# DOORLOCK_alter.net
KiCad netlist of a schematic drawn in EAGLE
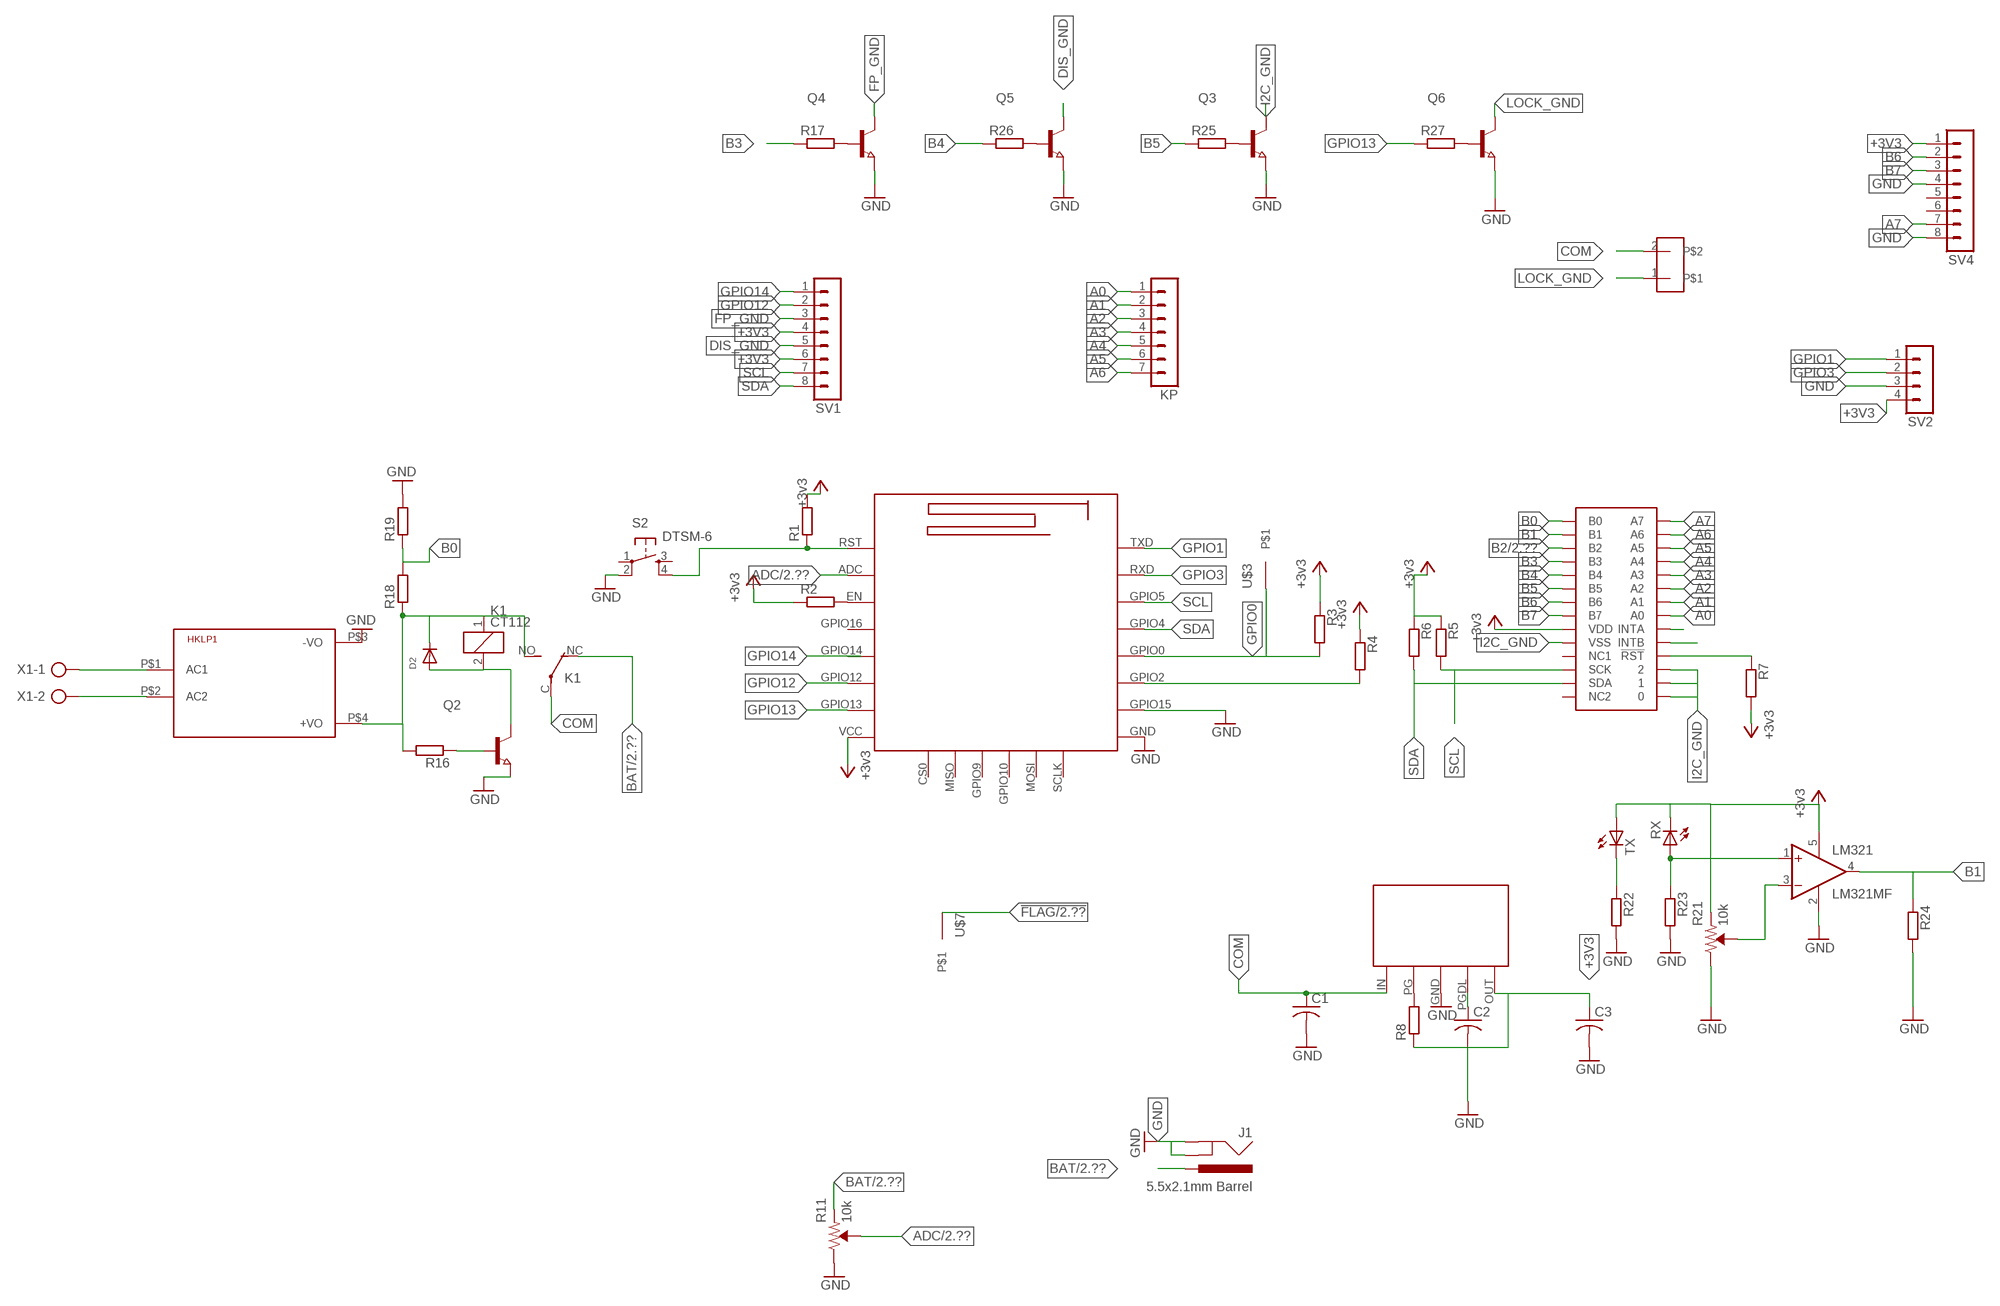
[diagram p0: schematic, sheet 1]
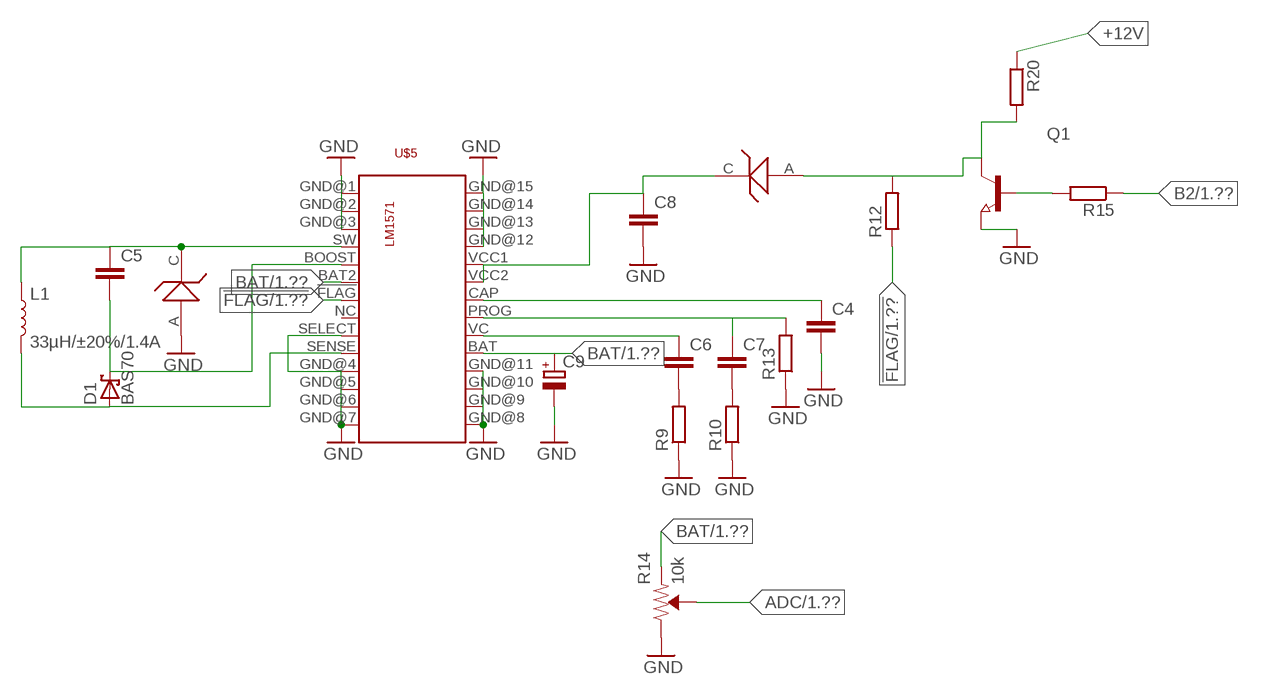
[diagram p1: schematic, sheet 2]

(export (version "E")
  (design (tool "Eeschema 10.0.6"))
  (components
    (comp (ref "C4")
      (value "C-EUC0805")
      (footprint "eagle-import:C0805")
      (libsource (lib "eagle-import") (part "C-EUC0805"))
    )
    (comp (ref "C5")
      (value "C-EUC0805")
      (footprint "eagle-import:C0805")
      (libsource (lib "eagle-import") (part "C-EUC0805"))
    )
    (comp (ref "C6")
      (value "C-EUC0805")
      (footprint "eagle-import:C0805")
      (libsource (lib "eagle-import") (part "C-EUC0805"))
    )
    (comp (ref "C7")
      (value "C-EUC0805")
      (footprint "eagle-import:C0805")
      (libsource (lib "eagle-import") (part "C-EUC0805"))
    )
    (comp (ref "C8")
      (value "C-EUC0805")
      (footprint "eagle-import:C0805")
      (libsource (lib "eagle-import") (part "C-EUC0805"))
    )
    (comp (ref "C9")
      (value "CPOL-EUCT3216")
      (footprint "eagle-import:CT3216")
      (libsource (lib "eagle-import") (part "CPOL-EUCT3216"))
    )
    (comp (ref "D1")
      (value "BAS70")
      (footprint "eagle-import:SOT23")
      (libsource (lib "eagle-import") (part "BAS70"))
    )
    (comp (ref "D3")
      (value "MBRM120T3")
      (footprint "eagle-import:MBRM120T3")
      (libsource (lib "eagle-import") (part "MBRM120T3"))
    )
    (comp (ref "L1")
      (value "33µH/±20%/1.4A")
      (footprint "eagle-import:SRN6045")
      (libsource (lib "eagle-import") (part "INDUCTOR-SRN6045-33UH"))
    )
    (comp (ref "Q1")
      (value "NPN-TRANSISTOR_SOT89")
      (footprint "eagle-import:SOT89")
      (libsource (lib "eagle-import") (part "NPN-TRANSISTOR_SOT89"))
    )
    (comp (ref "R9")
      (value "R-EU_0204/2V")
      (footprint "eagle-import:0204V")
      (libsource (lib "eagle-import") (part "R-EU_0204/2V"))
    )
    (comp (ref "R10")
      (value "R-EU_0204/2V")
      (footprint "eagle-import:0204V")
      (libsource (lib "eagle-import") (part "R-EU_0204/2V"))
    )
    (comp (ref "R12")
      (value "R-EU_0204/2V")
      (footprint "eagle-import:0204V")
      (libsource (lib "eagle-import") (part "R-EU_0204/2V"))
    )
    (comp (ref "R13")
      (value "R-EU_0204/2V")
      (footprint "eagle-import:0204V")
      (libsource (lib "eagle-import") (part "R-EU_0204/2V"))
    )
    (comp (ref "R14")
      (value "10k")
      (footprint "eagle-import:TRIMPOT-SMD-TC33X")
      (libsource (lib "eagle-import") (part "TRIMPOT-SMD-3MM-OPEN-1/10W-25%"))
    )
    (comp (ref "R15")
      (value "R-EU_0204/2V")
      (footprint "eagle-import:0204V")
      (libsource (lib "eagle-import") (part "R-EU_0204/2V"))
    )
    (comp (ref "R20")
      (value "R-EU_0204/2V")
      (footprint "eagle-import:0204V")
      (libsource (lib "eagle-import") (part "R-EU_0204/2V"))
    )
    (comp (ref "U$5")
      (value "LM1571")
      (footprint "eagle-import:LT1571")
      (libsource (lib "eagle-import") (part "LM1571"))
    )
    (comp (ref "U$6")
      (value "MBRM120T3")
      (footprint "eagle-import:MBRM120T3")
      (libsource (lib "eagle-import") (part "MBRM120T3"))
    )
    (comp (ref "C1")
      (value "C-USC1206")
      (footprint "eagle-import:C1206")
      (libsource (lib "eagle-import") (part "C-USC1206"))
    )
    (comp (ref "C2")
      (value "C-USC1206")
      (footprint "eagle-import:C1206")
      (libsource (lib "eagle-import") (part "C-USC1206"))
    )
    (comp (ref "C3")
      (value "C-USC1206")
      (footprint "eagle-import:C1206")
      (libsource (lib "eagle-import") (part "C-USC1206"))
    )
    (comp (ref "D2")
      (value "DIODESOD-123")
      (footprint "eagle-import:SOD-123")
      (libsource (lib "eagle-import") (part "DIODESOD-123"))
    )
    (comp (ref "HKLP1")
      (value "HKLPM01")
      (footprint "eagle-import:HKLPM01")
      (libsource (lib "eagle-import") (part "HKLPM01"))
    )
    (comp (ref "J1")
      (value "5.5x2.1mm Barrel")
      (footprint "eagle-import:POWER_JACK_SMD")
      (libsource (lib "eagle-import") (part "POWER_JACKSMD"))
    )
    (comp (ref "K1")
      (value "CT112")
      (footprint "eagle-import:CT-SLIM")
      (libsource (lib "eagle-import") (part "CT112"))
    )
    (comp (ref "KP")
      (value "MA07-1")
      (footprint "eagle-import:MA07-1")
      (libsource (lib "eagle-import") (part "MA07-1"))
    )
    (comp (ref "LM321")
      (value "LM321MF")
      (footprint "eagle-import:SOT23-5")
      (libsource (lib "eagle-import") (part "LM321?MF"))
    )
    (comp (ref "MP2014")
      (value "MP2014")
      (footprint "eagle-import:MP2014")
      (libsource (lib "eagle-import") (part "MP2014"))
    )
    (comp (ref "Q2")
      (value "NPN-TRANSISTOR_SOT89")
      (footprint "eagle-import:SOT89")
      (libsource (lib "eagle-import") (part "NPN-TRANSISTOR_SOT89"))
    )
    (comp (ref "Q3")
      (value "NPN-TRANSISTOR_SOT89")
      (footprint "eagle-import:SOT89")
      (libsource (lib "eagle-import") (part "NPN-TRANSISTOR_SOT89"))
    )
    (comp (ref "Q4")
      (value "NPN-TRANSISTOR_SOT89")
      (footprint "eagle-import:SOT89")
      (libsource (lib "eagle-import") (part "NPN-TRANSISTOR_SOT89"))
    )
    (comp (ref "Q5")
      (value "NPN-TRANSISTOR_SOT89")
      (footprint "eagle-import:SOT89")
      (libsource (lib "eagle-import") (part "NPN-TRANSISTOR_SOT89"))
    )
    (comp (ref "Q6")
      (value "NPN-TRANSISTOR_SOT89")
      (footprint "eagle-import:SOT89")
      (libsource (lib "eagle-import") (part "NPN-TRANSISTOR_SOT89"))
    )
    (comp (ref "R1")
      (value "R-EU_0204/2V")
      (footprint "eagle-import:0204V")
      (libsource (lib "eagle-import") (part "resistor_R-EU_0204/2V"))
    )
    (comp (ref "R2")
      (value "R-EU_0204/2V")
      (footprint "eagle-import:0204V")
      (libsource (lib "eagle-import") (part "resistor_R-EU_0204/2V"))
    )
    (comp (ref "R3")
      (value "R-EU_0204/2V")
      (footprint "eagle-import:0204V")
      (libsource (lib "eagle-import") (part "resistor_R-EU_0204/2V"))
    )
    (comp (ref "R4")
      (value "R-EU_0204/2V")
      (footprint "eagle-import:0204V")
      (libsource (lib "eagle-import") (part "resistor_R-EU_0204/2V"))
    )
    (comp (ref "R5")
      (value "R-EU_0204/2V")
      (footprint "eagle-import:0204V")
      (libsource (lib "eagle-import") (part "resistor_R-EU_0204/2V"))
    )
    (comp (ref "R6")
      (value "R-EU_0204/2V")
      (footprint "eagle-import:0204V")
      (libsource (lib "eagle-import") (part "resistor_R-EU_0204/2V"))
    )
    (comp (ref "R7")
      (value "R-EU_0204/2V")
      (footprint "eagle-import:0204V")
      (libsource (lib "eagle-import") (part "resistor_R-EU_0204/2V"))
    )
    (comp (ref "R8")
      (value "R-EU_0204/2V")
      (footprint "eagle-import:0204V")
      (libsource (lib "eagle-import") (part "resistor_R-EU_0204/2V"))
    )
    (comp (ref "R11")
      (value "10k")
      (footprint "eagle-import:TRIMPOT-SMD-TC33X")
      (libsource (lib "eagle-import") (part "TRIMPOT-SMD-3MM-OPEN-1/10W-25%"))
    )
    (comp (ref "R16")
      (value "R-EU_0204/2V")
      (footprint "eagle-import:0204V")
      (libsource (lib "eagle-import") (part "resistor_R-EU_0204/2V"))
    )
    (comp (ref "R17")
      (value "R-EU_0204/2V")
      (footprint "eagle-import:0204V")
      (libsource (lib "eagle-import") (part "resistor_R-EU_0204/2V"))
    )
    (comp (ref "R18")
      (value "R-EU_0204/2V")
      (footprint "eagle-import:0204V")
      (libsource (lib "eagle-import") (part "resistor_R-EU_0204/2V"))
    )
    (comp (ref "R19")
      (value "R-EU_0204/2V")
      (footprint "eagle-import:0204V")
      (libsource (lib "eagle-import") (part "resistor_R-EU_0204/2V"))
    )
    (comp (ref "R21")
      (value "10k")
      (footprint "eagle-import:TRIMPOT-SMD-TC33X")
      (libsource (lib "eagle-import") (part "TRIMPOT-SMD-3MM-OPEN-1/10W-25%"))
    )
    (comp (ref "R22")
      (value "R-EU_0204/2V")
      (footprint "eagle-import:0204V")
      (libsource (lib "eagle-import") (part "resistor_R-EU_0204/2V"))
    )
    (comp (ref "R23")
      (value "R-EU_0204/2V")
      (footprint "eagle-import:0204V")
      (libsource (lib "eagle-import") (part "resistor_R-EU_0204/2V"))
    )
    (comp (ref "R24")
      (value "R-EU_0204/2V")
      (footprint "eagle-import:0204V")
      (libsource (lib "eagle-import") (part "resistor_R-EU_0204/2V"))
    )
    (comp (ref "R25")
      (value "R-EU_0204/2V")
      (footprint "eagle-import:0204V")
      (libsource (lib "eagle-import") (part "resistor_R-EU_0204/2V"))
    )
    (comp (ref "R26")
      (value "R-EU_0204/2V")
      (footprint "eagle-import:0204V")
      (libsource (lib "eagle-import") (part "resistor_R-EU_0204/2V"))
    )
    (comp (ref "R27")
      (value "R-EU_0204/2V")
      (footprint "eagle-import:0204V")
      (libsource (lib "eagle-import") (part "resistor_R-EU_0204/2V"))
    )
    (comp (ref "RX")
      (value "LED5MM")
      (footprint "eagle-import:LED5MM")
      (libsource (lib "eagle-import") (part "LED5MM"))
    )
    (comp (ref "S2")
      (value "DTSM-6")
      (footprint "eagle-import:DTSM-6")
      (libsource (lib "eagle-import") (part "DTSM-6"))
    )
    (comp (ref "SV1")
      (value "MA08-1")
      (footprint "eagle-import:MA08-1")
      (libsource (lib "eagle-import") (part "MA08-1"))
    )
    (comp (ref "SV2")
      (value "MA04-1")
      (footprint "eagle-import:MA04-1")
      (libsource (lib "eagle-import") (part "MA04-1"))
    )
    (comp (ref "SV4")
      (value "MA08-1")
      (footprint "eagle-import:MA08-1")
      (libsource (lib "eagle-import") (part "MA08-1"))
    )
    (comp (ref "TX")
      (value "LED5MM")
      (footprint "eagle-import:LED5MM")
      (libsource (lib "eagle-import") (part "LED5MM"))
    )
    (comp (ref "U$1")
      (value "ESP12E")
      (footprint "eagle-import:ESP-12E")
      (libsource (lib "eagle-import") (part "ESP12E"))
    )
    (comp (ref "U$2")
      (value "MCF23017")
      (footprint "eagle-import:MAX23017")
      (libsource (lib "eagle-import") (part "MCF23017"))
    )
    (comp (ref "U$3") (value "M1") (footprint "eagle-import:M1") (libsource (lib "eagle-import") (part "M1")))
    (comp (ref "U$4")
      (value "MALE2PIN")
      (footprint "eagle-import:MALE2PIN")
      (libsource (lib "eagle-import") (part "MALE2PIN"))
    )
    (comp (ref "U$7") (value "M1") (footprint "eagle-import:M1") (libsource (lib "eagle-import") (part "M1")))
    (comp (ref "X1")
      (value "AK500/2-H")
      (footprint "eagle-import:AK500_2-H")
      (libsource (lib "eagle-import") (part "AK500/2-H"))
    )
  )
  (nets
    (net (code "1") (name "+3V3") (class "Default")
      (node (ref "C3") (pin "1") (pinfunction "1_1") (pintype "passive"))
      (node (ref "LM321") (pin "5") (pinfunction "V+_5") (pintype "power_in"))
      (node (ref "MP2014") (pin "OUT") (pinfunction "P$5_OUT") (pintype "bidirectional"))
      (node (ref "R1") (pin "2") (pinfunction "2_2") (pintype "passive"))
      (node (ref "R2") (pin "1") (pinfunction "1_1") (pintype "passive"))
      (node (ref "R21") (pin "3") (pinfunction "CCW_3") (pintype "passive"))
      (node (ref "R3") (pin "1") (pinfunction "1_1") (pintype "passive"))
      (node (ref "R4") (pin "1") (pinfunction "1_1") (pintype "passive"))
      (node (ref "R5") (pin "1") (pinfunction "1_1") (pintype "passive"))
      (node (ref "R6") (pin "1") (pinfunction "1_1") (pintype "passive"))
      (node (ref "R7") (pin "2") (pinfunction "2_2") (pintype "passive"))
      (node (ref "R8") (pin "1") (pinfunction "1_1") (pintype "passive"))
      (node (ref "RX") (pin "K") (pinfunction "C_K") (pintype "passive"))
      (node (ref "SV1") (pin "4") (pinfunction "4_4") (pintype "passive"))
      (node (ref "SV1") (pin "6") (pinfunction "6_6") (pintype "passive"))
      (node (ref "SV2") (pin "4") (pinfunction "4_4") (pintype "passive"))
      (node (ref "SV4") (pin "1") (pinfunction "1_1") (pintype "passive"))
      (node (ref "TX") (pin "A") (pinfunction "A_A") (pintype "passive"))
      (node (ref "U$1") (pin "VCC") (pinfunction "P$8_VCC") (pintype "bidirectional"))
      (node (ref "U$2") (pin "P$9") (pinfunction "VDD_P$9") (pintype "bidirectional"))
    )
    (net (code "2") (name "+12V") (class "Default")
      (node (ref "D2") (pin "C") (pinfunction "C_C") (pintype "passive"))
      (node (ref "HKLP1") (pin "P$4") (pinfunction "+VO_P$4") (pintype "bidirectional"))
      (node (ref "K1") (pin "1") (pinfunction "1_1") (pintype "passive"))
      (node (ref "K1") (pin "NO") (pinfunction "S_NO") (pintype "passive"))
      (node (ref "R16") (pin "2") (pinfunction "2_2") (pintype "passive"))
      (node (ref "R18") (pin "1") (pinfunction "1_1") (pintype "passive"))
      (node (ref "R20") (pin "1") (pinfunction "1_1") (pintype "passive"))
    )
    (net (code "3") (name "A0") (class "Default")
      (node (ref "KP") (pin "1") (pinfunction "1_1") (pintype "passive"))
      (node (ref "U$2") (pin "P$21") (pinfunction "A0_P$21") (pintype "bidirectional"))
    )
    (net (code "4") (name "A1") (class "Default")
      (node (ref "KP") (pin "2") (pinfunction "2_2") (pintype "passive"))
      (node (ref "U$2") (pin "P$22") (pinfunction "A1_P$22") (pintype "bidirectional"))
    )
    (net (code "5") (name "A2") (class "Default")
      (node (ref "KP") (pin "3") (pinfunction "3_3") (pintype "passive"))
      (node (ref "U$2") (pin "P$23") (pinfunction "A2_P$23") (pintype "bidirectional"))
    )
    (net (code "6") (name "A3") (class "Default")
      (node (ref "KP") (pin "4") (pinfunction "4_4") (pintype "passive"))
      (node (ref "U$2") (pin "P$24") (pinfunction "A3_P$24") (pintype "bidirectional"))
    )
    (net (code "7") (name "A4") (class "Default")
      (node (ref "KP") (pin "5") (pinfunction "5_5") (pintype "passive"))
      (node (ref "U$2") (pin "P$25") (pinfunction "A4_P$25") (pintype "bidirectional"))
    )
    (net (code "8") (name "A5") (class "Default")
      (node (ref "KP") (pin "6") (pinfunction "6_6") (pintype "passive"))
      (node (ref "U$2") (pin "P$26") (pinfunction "A5_P$26") (pintype "bidirectional"))
    )
    (net (code "9") (name "A6") (class "Default")
      (node (ref "KP") (pin "7") (pinfunction "7_7") (pintype "passive"))
      (node (ref "U$2") (pin "P$27") (pinfunction "A6_P$27") (pintype "bidirectional"))
    )
    (net (code "10") (name "A7") (class "Default")
      (node (ref "SV4") (pin "7") (pinfunction "7_7") (pintype "passive"))
      (node (ref "U$2") (pin "P$28") (pinfunction "A7_P$28") (pintype "bidirectional"))
    )
    (net (code "11") (name "ADC") (class "Default")
      (node (ref "R11") (pin "2") (pinfunction "WIPER_2") (pintype "passive"))
      (node (ref "R14") (pin "2") (pinfunction "WIPER_2") (pintype "passive"))
      (node (ref "U$1") (pin "ADC") (pinfunction "P$2_ADC") (pintype "bidirectional"))
    )
    (net (code "12") (name "B0") (class "Default")
      (node (ref "R18") (pin "2") (pinfunction "2_2") (pintype "passive"))
      (node (ref "R19") (pin "1") (pinfunction "1_1") (pintype "passive"))
      (node (ref "U$2") (pin "P$1") (pinfunction "B0_P$1") (pintype "bidirectional"))
    )
    (net (code "13") (name "B1") (class "Default")
      (node (ref "LM321") (pin "4") (pinfunction "OUT_4") (pintype "output"))
      (node (ref "R24") (pin "1") (pinfunction "1_1") (pintype "passive"))
      (node (ref "U$2") (pin "P$2") (pinfunction "B1_P$2") (pintype "bidirectional"))
    )
    (net (code "14") (name "B2") (class "Default")
      (node (ref "R15") (pin "1") (pinfunction "1_1") (pintype "passive"))
      (node (ref "U$2") (pin "P$3") (pinfunction "B2_P$3") (pintype "bidirectional"))
    )
    (net (code "15") (name "B3") (class "Default")
      (node (ref "R17") (pin "1") (pinfunction "1_1") (pintype "passive"))
      (node (ref "U$2") (pin "P$4") (pinfunction "B3_P$4") (pintype "bidirectional"))
    )
    (net (code "16") (name "B4") (class "Default")
      (node (ref "R26") (pin "1") (pinfunction "1_1") (pintype "passive"))
      (node (ref "U$2") (pin "P$5") (pinfunction "B4_P$5") (pintype "bidirectional"))
    )
    (net (code "17") (name "B5") (class "Default")
      (node (ref "R25") (pin "1") (pinfunction "1_1") (pintype "passive"))
      (node (ref "U$2") (pin "P$6") (pinfunction "B5_P$6") (pintype "bidirectional"))
    )
    (net (code "18") (name "B6") (class "Default")
      (node (ref "SV4") (pin "2") (pinfunction "2_2") (pintype "passive"))
      (node (ref "U$2") (pin "P$7") (pinfunction "B6_P$7") (pintype "bidirectional"))
    )
    (net (code "19") (name "B7") (class "Default")
      (node (ref "SV4") (pin "3") (pinfunction "3_3") (pintype "passive"))
      (node (ref "U$2") (pin "P$8") (pinfunction "B7_P$8") (pintype "bidirectional"))
    )
    (net (code "20") (name "BAT") (class "Default")
      (node (ref "C9") (pin "+") (pinfunction "+_+") (pintype "passive"))
      (node (ref "J1") (pin "VIN0") (pinfunction "PWR_VIN0") (pintype "bidirectional"))
      (node (ref "K1") (pin "NC") (pinfunction "O_NC") (pintype "passive"))
      (node (ref "R11") (pin "3") (pinfunction "CCW_3") (pintype "passive"))
      (node (ref "R14") (pin "3") (pinfunction "CCW_3") (pintype "passive"))
      (node (ref "U$5") (pin "BAT") (pinfunction "P$19_BAT") (pintype "bidirectional"))
      (node (ref "U$5") (pin "BAT2") (pinfunction "P$6_BAT2") (pintype "bidirectional"))
    )
    (net (code "21") (name "COM") (class "Default")
      (node (ref "C1") (pin "1") (pinfunction "1_1") (pintype "passive"))
      (node (ref "K1") (pin "C") (pinfunction "P_C") (pintype "passive"))
      (node (ref "MP2014") (pin "IN") (pinfunction "P$1_IN") (pintype "bidirectional"))
      (node (ref "U$4") (pin "2") (pinfunction "P$2_2") (pintype "bidirectional"))
    )
    (net (code "22") (name "DIS_GND") (class "Default")
      (node (ref "Q5") (pin "2") (pinfunction "C_2") (pintype "passive"))
      (node (ref "SV1") (pin "5") (pinfunction "5_5") (pintype "passive"))
    )
    (net (code "23") (name "FP_GND") (class "Default")
      (node (ref "Q4") (pin "2") (pinfunction "C_2") (pintype "passive"))
      (node (ref "SV1") (pin "3") (pinfunction "3_3") (pintype "passive"))
    )
    (net (code "24") (name "GND") (class "Default")
      (node (ref "C1") (pin "2") (pinfunction "2_2") (pintype "passive"))
      (node (ref "C2") (pin "2") (pinfunction "2_2") (pintype "passive"))
      (node (ref "C3") (pin "2") (pinfunction "2_2") (pintype "passive"))
      (node (ref "C4") (pin "2") (pinfunction "2_2") (pintype "passive"))
      (node (ref "C8") (pin "2") (pinfunction "2_2") (pintype "passive"))
      (node (ref "C9") (pin "-") (pinfunction "-_-") (pintype "passive"))
      (node (ref "HKLP1") (pin "P$3") (pinfunction "-VO_P$3") (pintype "bidirectional"))
      (node (ref "J1") (pin "GND") (pinfunction "GNDBREAK_GND") (pintype "bidirectional"))
      (node (ref "J1") (pin "P$4") (pinfunction "GND_P$4") (pintype "bidirectional"))
      (node (ref "LM321") (pin "2") (pinfunction "V-_2") (pintype "power_in"))
      (node (ref "MP2014") (pin "GND") (pinfunction "P$3_GND") (pintype "bidirectional"))
      (node (ref "Q1") (pin "3") (pinfunction "E_3") (pintype "passive"))
      (node (ref "Q2") (pin "3") (pinfunction "E_3") (pintype "passive"))
      (node (ref "Q3") (pin "3") (pinfunction "E_3") (pintype "passive"))
      (node (ref "Q4") (pin "3") (pinfunction "E_3") (pintype "passive"))
      (node (ref "Q5") (pin "3") (pinfunction "E_3") (pintype "passive"))
      (node (ref "Q6") (pin "3") (pinfunction "E_3") (pintype "passive"))
      (node (ref "R10") (pin "1") (pinfunction "1_1") (pintype "passive"))
      (node (ref "R11") (pin "1") (pinfunction "CW_1") (pintype "passive"))
      (node (ref "R13") (pin "1") (pinfunction "1_1") (pintype "passive"))
      (node (ref "R14") (pin "1") (pinfunction "CW_1") (pintype "passive"))
      (node (ref "R19") (pin "2") (pinfunction "2_2") (pintype "passive"))
      (node (ref "R21") (pin "1") (pinfunction "CW_1") (pintype "passive"))
      (node (ref "R22") (pin "2") (pinfunction "2_2") (pintype "passive"))
      (node (ref "R23") (pin "2") (pinfunction "2_2") (pintype "passive"))
      (node (ref "R24") (pin "2") (pinfunction "2_2") (pintype "passive"))
      (node (ref "R9") (pin "1") (pinfunction "1_1") (pintype "passive"))
      (node (ref "S2") (pin "2") (pinfunction "2_2") (pintype "passive"))
      (node (ref "SV2") (pin "3") (pinfunction "3_3") (pintype "passive"))
      (node (ref "SV4") (pin "4") (pinfunction "4_4") (pintype "passive"))
      (node (ref "SV4") (pin "8") (pinfunction "8_8") (pintype "passive"))
      (node (ref "U$1") (pin "GND") (pinfunction "P$15_GND") (pintype "bidirectional"))
      (node (ref "U$1") (pin "GPIO15") (pinfunction "P$16_GPIO15") (pintype "bidirectional"))
      (node (ref "U$5") (pin "GND@1") (pinfunction "P$1_GND@1") (pintype "bidirectional"))
      (node (ref "U$5") (pin "GND@10") (pinfunction "P$17_GND@10") (pintype "bidirectional"))
      (node (ref "U$5") (pin "GND@11") (pinfunction "P$18_GND@11") (pintype "bidirectional"))
      (node (ref "U$5") (pin "GND@12") (pinfunction "P$25_GND@12") (pintype "bidirectional"))
      (node (ref "U$5") (pin "GND@13") (pinfunction "P$26_GND@13") (pintype "bidirectional"))
      (node (ref "U$5") (pin "GND@14") (pinfunction "P$27_GND@14") (pintype "bidirectional"))
      (node (ref "U$5") (pin "GND@15") (pinfunction "P$28_GND@15") (pintype "bidirectional"))
      (node (ref "U$5") (pin "GND@2") (pinfunction "P$2_GND@2") (pintype "bidirectional"))
      (node (ref "U$5") (pin "GND@3") (pinfunction "P$3_GND@3") (pintype "bidirectional"))
      (node (ref "U$5") (pin "GND@4") (pinfunction "P$11_GND@4") (pintype "bidirectional"))
      (node (ref "U$5") (pin "GND@5") (pinfunction "P$12_GND@5") (pintype "bidirectional"))
      (node (ref "U$5") (pin "GND@6") (pinfunction "P$13_GND@6") (pintype "bidirectional"))
      (node (ref "U$5") (pin "GND@7") (pinfunction "P$14_GND@7") (pintype "bidirectional"))
      (node (ref "U$5") (pin "GND@8") (pinfunction "P$15_GND@8") (pintype "bidirectional"))
      (node (ref "U$5") (pin "GND@9") (pinfunction "P$16_GND@9") (pintype "bidirectional"))
      (node (ref "U$5") (pin "SELECT") (pinfunction "P$9_SELECT") (pintype "bidirectional"))
      (node (ref "U$6") (pin "A") (pinfunction "A_A") (pintype "bidirectional"))
    )
    (net (code "25") (name "GPIO0") (class "Default")
      (node (ref "R3") (pin "2") (pinfunction "2_2") (pintype "passive"))
      (node (ref "U$1") (pin "GPIO0") (pinfunction "P$18_GPIO0") (pintype "bidirectional"))
      (node (ref "U$3") (pin "P$1") (pinfunction "P$1_P$1") (pintype "bidirectional"))
    )
    (net (code "26") (name "GPIO1") (class "Default")
      (node (ref "SV2") (pin "1") (pinfunction "1_1") (pintype "passive"))
      (node (ref "U$1") (pin "TXD") (pinfunction "P$22_TXD") (pintype "bidirectional"))
    )
    (net (code "27") (name "GPIO3") (class "Default")
      (node (ref "SV2") (pin "2") (pinfunction "2_2") (pintype "passive"))
      (node (ref "U$1") (pin "RXD") (pinfunction "P$21_RXD") (pintype "bidirectional"))
    )
    (net (code "28") (name "GPIO12") (class "Default")
      (node (ref "SV1") (pin "2") (pinfunction "2_2") (pintype "passive"))
      (node (ref "U$1") (pin "GPIO12") (pinfunction "P$6_GPIO12") (pintype "bidirectional"))
    )
    (net (code "29") (name "GPIO13") (class "Default")
      (node (ref "R27") (pin "1") (pinfunction "1_1") (pintype "passive"))
      (node (ref "U$1") (pin "GPIO13") (pinfunction "P$7_GPIO13") (pintype "bidirectional"))
    )
    (net (code "30") (name "GPIO14") (class "Default")
      (node (ref "SV1") (pin "1") (pinfunction "1_1") (pintype "passive"))
      (node (ref "U$1") (pin "GPIO14") (pinfunction "P$5_GPIO14") (pintype "bidirectional"))
    )
    (net (code "31") (name "I2C_GND") (class "Default")
      (node (ref "Q3") (pin "2") (pinfunction "C_2") (pintype "passive"))
      (node (ref "U$2") (pin "P$10") (pinfunction "VSS_P$10") (pintype "bidirectional"))
      (node (ref "U$2") (pin "P$15") (pinfunction "0_P$15") (pintype "bidirectional"))
      (node (ref "U$2") (pin "P$16") (pinfunction "1_P$16") (pintype "bidirectional"))
      (node (ref "U$2") (pin "P$17") (pinfunction "2_P$17") (pintype "bidirectional"))
    )
    (net (code "32") (name "LOCK_GND") (class "Default")
      (node (ref "Q6") (pin "2") (pinfunction "C_2") (pintype "passive"))
      (node (ref "U$4") (pin "1") (pinfunction "P$1_1") (pintype "bidirectional"))
    )
    (net (code "33") (name "Net-(C6-Pad2)") (class "Default")
      (node (ref "C6") (pin "2") (pinfunction "2_2") (pintype "passive"))
      (node (ref "R9") (pin "2") (pinfunction "2_2") (pintype "passive"))
    )
    (net (code "34") (name "Net-(C7-Pad2)") (class "Default")
      (node (ref "C7") (pin "2") (pinfunction "2_2") (pintype "passive"))
      (node (ref "R10") (pin "2") (pinfunction "2_2") (pintype "passive"))
    )
    (net (code "35") (name "Net-(D1-A)") (class "Default")
      (node (ref "D1") (pin "1") (pinfunction "A_1") (pintype "passive"))
      (node (ref "L1") (pin "2") (pinfunction "2_2") (pintype "passive"))
      (node (ref "U$5") (pin "SENSE") (pinfunction "P$10_SENSE") (pintype "bidirectional"))
    )
    (net (code "36") (name "Net-(D1-C)") (class "Default")
      (node (ref "C5") (pin "2") (pinfunction "2_2") (pintype "passive"))
      (node (ref "D1") (pin "3") (pinfunction "C_3") (pintype "passive"))
      (node (ref "U$5") (pin "BOOST") (pinfunction "P$5_BOOST") (pintype "bidirectional"))
    )
    (net (code "37") (name "Net-(HKLP1-AC1)") (class "Default")
      (node (ref "HKLP1") (pin "P$1") (pinfunction "AC1_P$1") (pintype "bidirectional"))
      (node (ref "X1") (pin "1") (pinfunction "KL_1") (pintype "passive"))
    )
    (net (code "38") (name "Net-(HKLP1-AC2)") (class "Default")
      (node (ref "HKLP1") (pin "P$2") (pinfunction "AC2_P$2") (pintype "bidirectional"))
      (node (ref "X1") (pin "2") (pinfunction "KL_2") (pintype "passive"))
    )
    (net (code "39") (name "Net-(LM321-+IN)") (class "Default")
      (node (ref "LM321") (pin "1") (pinfunction "+IN_1") (pintype "input"))
      (node (ref "R23") (pin "1") (pinfunction "1_1") (pintype "passive"))
      (node (ref "RX") (pin "A") (pinfunction "A_A") (pintype "passive"))
    )
    (net (code "40") (name "Net-(LM321--IN)") (class "Default")
      (node (ref "LM321") (pin "3") (pinfunction "-IN_3") (pintype "input"))
      (node (ref "R21") (pin "2") (pinfunction "WIPER_2") (pintype "passive"))
    )
    (net (code "41") (name "Net-(MP2014-P$2)") (class "Default")
      (node (ref "MP2014") (pin "PG") (pinfunction "P$2_PG") (pintype "bidirectional"))
      (node (ref "R8") (pin "2") (pinfunction "2_2") (pintype "passive"))
    )
    (net (code "42") (name "Net-(MP2014-P$4)") (class "Default")
      (node (ref "C2") (pin "1") (pinfunction "1_1") (pintype "passive"))
      (node (ref "MP2014") (pin "PGDL") (pinfunction "P$4_PGDL") (pintype "bidirectional"))
    )
    (net (code "43") (name "Net-(Q1-B)") (class "Default")
      (node (ref "Q1") (pin "1") (pinfunction "B_1") (pintype "passive"))
      (node (ref "R15") (pin "2") (pinfunction "2_2") (pintype "passive"))
    )
    (net (code "44") (name "Net-(Q1-C)") (class "Default")
      (node (ref "D3") (pin "A") (pinfunction "A_A") (pintype "bidirectional"))
      (node (ref "Q1") (pin "2") (pinfunction "C_2") (pintype "passive"))
      (node (ref "R12") (pin "2") (pinfunction "2_2") (pintype "passive"))
      (node (ref "R20") (pin "2") (pinfunction "2_2") (pintype "passive"))
    )
    (net (code "45") (name "Net-(Q2-B)") (class "Default")
      (node (ref "Q2") (pin "1") (pinfunction "B_1") (pintype "passive"))
      (node (ref "R16") (pin "1") (pinfunction "1_1") (pintype "passive"))
    )
    (net (code "46") (name "Net-(Q2-C)") (class "Default")
      (node (ref "D2") (pin "A") (pinfunction "A_A") (pintype "passive"))
      (node (ref "K1") (pin "2") (pinfunction "2_2") (pintype "passive"))
      (node (ref "Q2") (pin "2") (pinfunction "C_2") (pintype "passive"))
    )
    (net (code "47") (name "Net-(Q3-B)") (class "Default")
      (node (ref "Q3") (pin "1") (pinfunction "B_1") (pintype "passive"))
      (node (ref "R25") (pin "2") (pinfunction "2_2") (pintype "passive"))
    )
    (net (code "48") (name "Net-(Q4-B)") (class "Default")
      (node (ref "Q4") (pin "1") (pinfunction "B_1") (pintype "passive"))
      (node (ref "R17") (pin "2") (pinfunction "2_2") (pintype "passive"))
    )
    (net (code "49") (name "Net-(Q5-B)") (class "Default")
      (node (ref "Q5") (pin "1") (pinfunction "B_1") (pintype "passive"))
      (node (ref "R26") (pin "2") (pinfunction "2_2") (pintype "passive"))
    )
    (net (code "50") (name "Net-(Q6-B)") (class "Default")
      (node (ref "Q6") (pin "1") (pinfunction "B_1") (pintype "passive"))
      (node (ref "R27") (pin "2") (pinfunction "2_2") (pintype "passive"))
    )
    (net (code "51") (name "Net-(TX-C)") (class "Default")
      (node (ref "R22") (pin "1") (pinfunction "1_1") (pintype "passive"))
      (node (ref "TX") (pin "K") (pinfunction "C_K") (pintype "passive"))
    )
    (net (code "52") (name "Net-(U$1-P$1)") (class "Default")
      (node (ref "R1") (pin "1") (pinfunction "1_1") (pintype "passive"))
      (node (ref "S2") (pin "4") (pinfunction "4_4") (pintype "passive"))
      (node (ref "U$1") (pin "RST") (pinfunction "P$1_RST") (pintype "bidirectional"))
    )
    (net (code "53") (name "Net-(U$1-P$3)") (class "Default")
      (node (ref "R2") (pin "2") (pinfunction "2_2") (pintype "passive"))
      (node (ref "U$1") (pin "EN") (pinfunction "P$3_EN") (pintype "bidirectional"))
    )
    (net (code "54") (name "Net-(U$1-P$17)") (class "Default")
      (node (ref "R4") (pin "2") (pinfunction "2_2") (pintype "passive"))
      (node (ref "U$1") (pin "GPIO2") (pinfunction "P$17_GPIO2") (pintype "bidirectional"))
    )
    (net (code "55") (name "Net-(U$2-~{RST})") (class "Default")
      (node (ref "R7") (pin "1") (pinfunction "1_1") (pintype "passive"))
      (node (ref "U$2") (pin "P$18") (pinfunction "~{RST}_P$18") (pintype "bidirectional"))
    )
    (net (code "56") (name "Net-(U$5-P$4)") (class "Default")
      (node (ref "C5") (pin "1") (pinfunction "1_1") (pintype "passive"))
      (node (ref "L1") (pin "1") (pinfunction "1_1") (pintype "passive"))
      (node (ref "U$5") (pin "SW") (pinfunction "P$4_SW") (pintype "bidirectional"))
      (node (ref "U$6") (pin "C") (pinfunction "C_C") (pintype "bidirectional"))
    )
    (net (code "57") (name "Net-(U$5-P$20)") (class "Default")
      (node (ref "C6") (pin "1") (pinfunction "1_1") (pintype "passive"))
      (node (ref "U$5") (pin "VC") (pinfunction "P$20_VC") (pintype "bidirectional"))
    )
    (net (code "58") (name "Net-(U$5-P$21)") (class "Default")
      (node (ref "C7") (pin "1") (pinfunction "1_1") (pintype "passive"))
      (node (ref "R13") (pin "2") (pinfunction "2_2") (pintype "passive"))
      (node (ref "U$5") (pin "PROG") (pinfunction "P$21_PROG") (pintype "bidirectional"))
    )
    (net (code "59") (name "Net-(U$5-P$22)") (class "Default")
      (node (ref "C4") (pin "1") (pinfunction "1_1") (pintype "passive"))
      (node (ref "U$5") (pin "CAP") (pinfunction "P$22_CAP") (pintype "bidirectional"))
    )
    (net (code "60") (name "Net-(U$5-P$23)") (class "Default")
      (node (ref "C8") (pin "1") (pinfunction "1_1") (pintype "passive"))
      (node (ref "D3") (pin "C") (pinfunction "C_C") (pintype "bidirectional"))
      (node (ref "U$5") (pin "VCC1") (pinfunction "P$24_VCC1") (pintype "bidirectional"))
      (node (ref "U$5") (pin "VCC2") (pinfunction "P$23_VCC2") (pintype "bidirectional"))
    )
    (net (code "61") (name "SCL") (class "Default")
      (node (ref "R5") (pin "2") (pinfunction "2_2") (pintype "passive"))
      (node (ref "SV1") (pin "7") (pinfunction "7_7") (pintype "passive"))
      (node (ref "U$1") (pin "GPIO5") (pinfunction "P$20_GPIO5") (pintype "bidirectional"))
      (node (ref "U$2") (pin "P$12") (pinfunction "SCK_P$12") (pintype "bidirectional"))
    )
    (net (code "62") (name "SDA") (class "Default")
      (node (ref "R6") (pin "2") (pinfunction "2_2") (pintype "passive"))
      (node (ref "SV1") (pin "8") (pinfunction "8_8") (pintype "passive"))
      (node (ref "U$1") (pin "GPIO4") (pinfunction "P$19_GPIO4") (pintype "bidirectional"))
      (node (ref "U$2") (pin "P$13") (pinfunction "SDA_P$13") (pintype "bidirectional"))
    )
    (net (code "63") (name "unconnected-(S2-Pad1)") (class "Default")
      (node (ref "S2") (pin "1") (pinfunction "1_1") (pintype "passive"))
    )
    (net (code "64") (name "unconnected-(S2-Pad3)") (class "Default")
      (node (ref "S2") (pin "3") (pinfunction "3_3") (pintype "passive"))
    )
    (net (code "65") (name "unconnected-(SV4-Pad5)") (class "Default")
      (node (ref "SV4") (pin "5") (pinfunction "5_5") (pintype "passive"))
    )
    (net (code "66") (name "unconnected-(SV4-Pad6)") (class "Default")
      (node (ref "SV4") (pin "6") (pinfunction "6_6") (pintype "passive"))
    )
    (net (code "67") (name "unconnected-(U$1-P$4-PadGPIO16)") (class "Default")
      (node (ref "U$1") (pin "GPIO16") (pinfunction "P$4_GPIO16") (pintype "bidirectional"))
    )
    (net (code "68") (name "unconnected-(U$1-P$9-PadCS0)") (class "Default")
      (node (ref "U$1") (pin "CS0") (pinfunction "P$9_CS0") (pintype "bidirectional"))
    )
    (net (code "69") (name "unconnected-(U$1-P$10-PadMISO)") (class "Default")
      (node (ref "U$1") (pin "MISO") (pinfunction "P$10_MISO") (pintype "bidirectional"))
    )
    (net (code "70") (name "unconnected-(U$1-P$11-PadGPIO9)") (class "Default")
      (node (ref "U$1") (pin "GPIO9") (pinfunction "P$11_GPIO9") (pintype "bidirectional"))
    )
    (net (code "71") (name "unconnected-(U$1-P$12-PadGPIO10)") (class "Default")
      (node (ref "U$1") (pin "GPIO10") (pinfunction "P$12_GPIO10") (pintype "bidirectional"))
    )
    (net (code "72") (name "unconnected-(U$1-P$13-PadMOSI)") (class "Default")
      (node (ref "U$1") (pin "MOSI") (pinfunction "P$13_MOSI") (pintype "bidirectional"))
    )
    (net (code "73") (name "unconnected-(U$1-P$14-PadSCLK)") (class "Default")
      (node (ref "U$1") (pin "SCLK") (pinfunction "P$14_SCLK") (pintype "bidirectional"))
    )
    (net (code "74") (name "unconnected-(U$2-INTA-PadP$20)") (class "Default")
      (node (ref "U$2") (pin "P$20") (pinfunction "INTA_P$20") (pintype "bidirectional"))
    )
    (net (code "75") (name "unconnected-(U$2-INTB-PadP$19)") (class "Default")
      (node (ref "U$2") (pin "P$19") (pinfunction "INTB_P$19") (pintype "bidirectional"))
    )
    (net (code "76") (name "unconnected-(U$2-NC1-PadP$11)") (class "Default")
      (node (ref "U$2") (pin "P$11") (pinfunction "NC1_P$11") (pintype "bidirectional"))
    )
    (net (code "77") (name "unconnected-(U$2-NC2-PadP$14)") (class "Default")
      (node (ref "U$2") (pin "P$14") (pinfunction "NC2_P$14") (pintype "bidirectional"))
    )
    (net (code "78") (name "unconnected-(U$5-P$8-PadNC)") (class "Default")
      (node (ref "U$5") (pin "NC") (pinfunction "P$8_NC") (pintype "bidirectional"))
    )
    (net (code "79") (name "~{FLAG}") (class "Default")
      (node (ref "R12") (pin "1") (pinfunction "1_1") (pintype "passive"))
      (node (ref "U$5") (pin "!FLAG") (pinfunction "P$7_!FLAG") (pintype "bidirectional"))
      (node (ref "U$7") (pin "P$1") (pinfunction "P$1_P$1") (pintype "bidirectional"))
    )
  )
)
